# SCH_protopanda_v7.net
KiCad netlist of a schematic drawn in EasyEDA
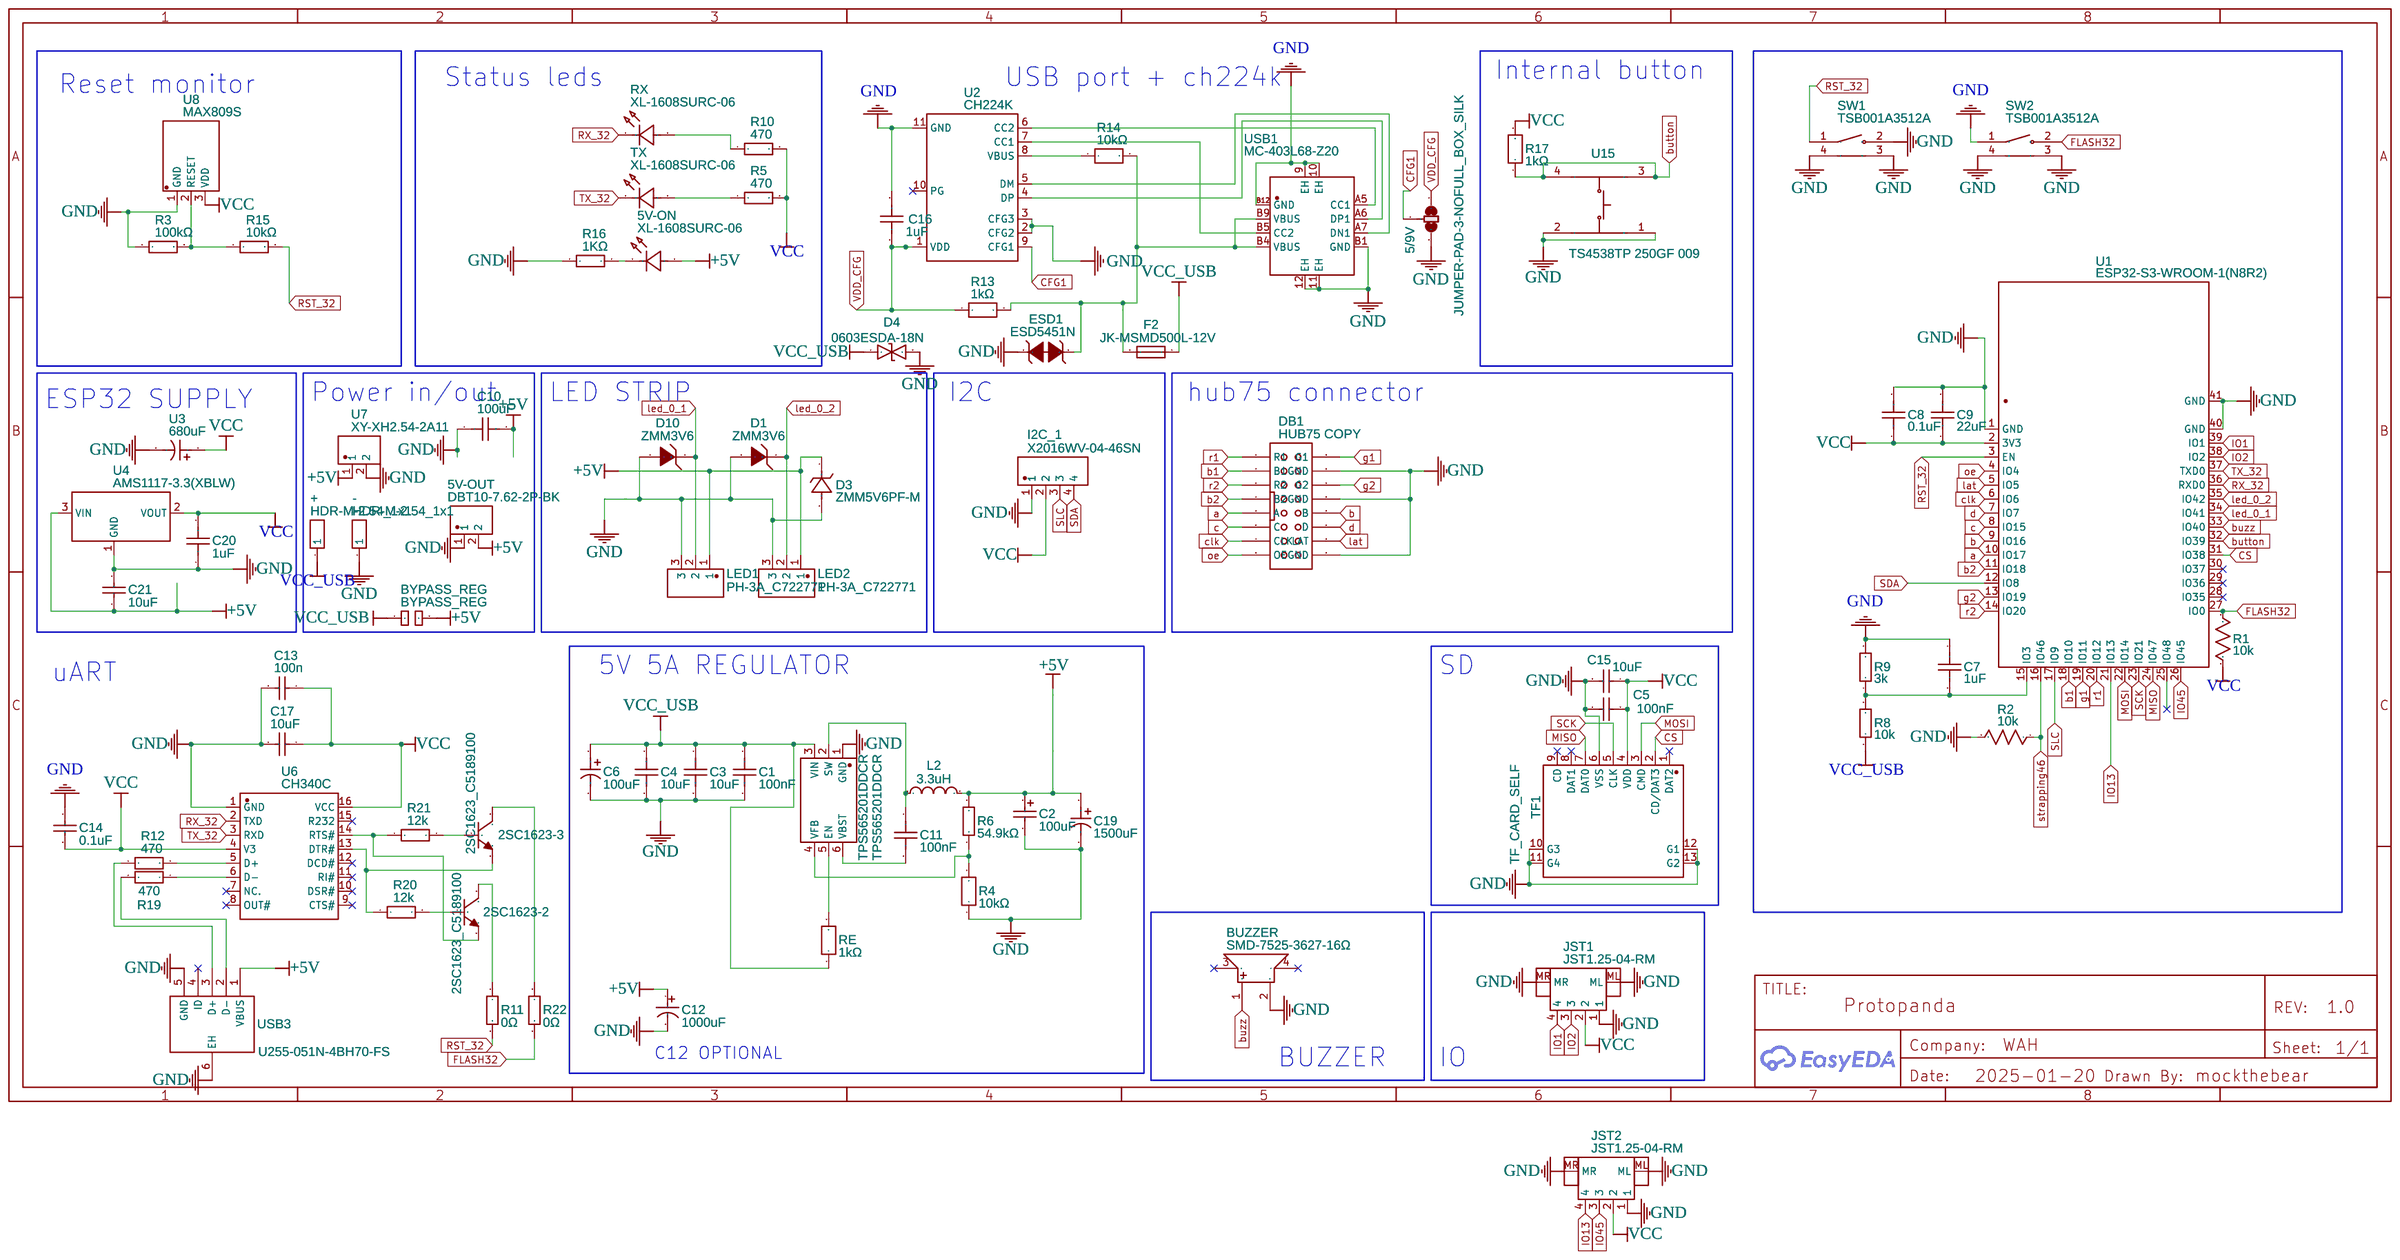
[diagram p0: schematic sheet]

(export (version "E")
  (design (tool "Eeschema 10.0.6"))
  (components
    (comp (ref "+") (value "HDR-M-2.54_1x1") (libsource (lib "") (part "HDR-M-2.54_1x1")))
    (comp (ref "-") (value "HDR-M-2.54_1x1") (libsource (lib "") (part "HDR-M-2.54_1x1_1")))
    (comp (ref "2SC1623-2")
      (value "2SC1623_C5189100")
      (fields (field (name "Manufacturer Part") "2SC1623") (field (name "Manufacturer") "HXY MOSFET(华轩阳电子)"))
      (libsource (lib "") (part "2SC1623_C5189100"))
    )
    (comp (ref "2SC1623-3")
      (value "2SC1623_C5189100")
      (fields (field (name "Manufacturer Part") "2SC1623") (field (name "Manufacturer") "HXY MOSFET(华轩阳电子)"))
      (libsource (lib "") (part "2SC1623_C5189100"))
    )
    (comp (ref "5/9V")
      (value "JUMPER-PAD-3-NOFULL_BOX_SILK")
      (libsource (lib "") (part "JUMPER-PAD-3-NOFULL_BOX_SILK"))
    )
    (comp (ref "5V-ON")
      (value "XL-1608SURC-06")
      (fields (field (name "Manufacturer") "XINGLIGHT(成兴光)"))
      (libsource (lib "") (part "XL-1608SURC-06_1"))
    )
    (comp (ref "5V-OUT")
      (value "DBT10-7.62-2P-BK")
      (fields
        (field (name "Manufacturer Part") "DBT10-7.62-2P-BK-P")
        (field (name "Manufacturer") "DIBO(地博电气)")
      )
      (libsource (lib "") (part "DBT10-7.62-2P-BK"))
    )
    (comp (ref "BUZZER")
      (value "SMD-7525-3627-16Ω")
      (fields (field (name "Manufacturer") "S&S(海旭)"))
      (libsource (lib "") (part "SMD-7525-3627-16Ω"))
    )
    (comp (ref "BYPASS_REG") (value "BYPASS_REG") (libsource (lib "") (part "Jumper_Pad_2")))
    (comp (ref "C1")
      (value "100nF")
      (fields (field (name "Manufacturer Part") "CC0603CRNPO9BN5R1") (field (name "Manufacturer") "YAGEO"))
      (libsource (lib "") (part "CC0603CRNPO9BN5R1"))
    )
    (comp (ref "C2")
      (value "100uF")
      (fields
        (field (name "Manufacturer Part") "T490A107M006ATE800")
        (field (name "Manufacturer") "KEMET(基美)")
      )
      (libsource (lib "") (part "T490A107M006ATE800"))
    )
    (comp (ref "C3")
      (value "10uF")
      (fields (field (name "Manufacturer Part") "CC0603CRNPO9BN5R1") (field (name "Manufacturer") "YAGEO"))
      (libsource (lib "") (part "CC0603CRNPO9BN5R1"))
    )
    (comp (ref "C4")
      (value "10uF")
      (fields (field (name "Manufacturer Part") "CC0603CRNPO9BN5R1") (field (name "Manufacturer") "YAGEO"))
      (libsource (lib "") (part "CC0603CRNPO9BN5R1"))
    )
    (comp (ref "C5")
      (value "100nF")
      (fields (field (name "Manufacturer Part") "C0603X104K101T") (field (name "Manufacturer") "HEC"))
      (libsource (lib "") (part "C0603X104K101T"))
    )
    (comp (ref "C6")
      (value "100uF")
      (fields
        (field (name "Manufacturer Part") "RVT100UF25V67RV0011")
        (field (name "Manufacturer") "KNSCHA(科尼盛)")
      )
      (libsource (lib "") (part "RVT100UF25V67RV0011"))
    )
    (comp (ref "C7")
      (value "1uF")
      (fields
        (field (name "Manufacturer Part") "CS1608X7R105K250NRB")
        (field (name "Manufacturer") "Samwha Capacitor")
      )
      (libsource (lib "") (part "CS1608X7R105K250NRB_1"))
    )
    (comp (ref "C8")
      (value "0.1uF")
      (fields
        (field (name "Manufacturer Part") "0603BB104K500NGT")
        (field (name "Manufacturer") "Knowles(楼氏)")
      )
      (libsource (lib "") (part "0603BB104K500NGT"))
    )
    (comp (ref "C9")
      (value "22uF")
      (fields
        (field (name "Manufacturer Part") "GRM188R61A226ME15D")
        (field (name "Manufacturer") "muRata(村田)")
      )
      (libsource (lib "") (part "GRM188R61A226ME15D"))
    )
    (comp (ref "C10")
      (value "100uF")
      (fields
        (field (name "Manufacturer Part") "TCC1206X5R107M6R3HT")
        (field (name "Manufacturer") "CCTC(三环)")
      )
      (libsource (lib "") (part "TCC1206X5R107M6R3HT"))
    )
    (comp (ref "C11")
      (value "100nF")
      (fields (field (name "Manufacturer Part") "CC0603CRNPO9BN5R1") (field (name "Manufacturer") "YAGEO"))
      (libsource (lib "") (part "CC0603CRNPO9BN5R1"))
    )
    (comp (ref "C12")
      (value "1000uF")
      (fields
        (field (name "Manufacturer Part") "EEU-FC2A101")
        (field (name "Manufacturer") "Panasonic Electronic Components")
      )
      (libsource (lib "") (part "electrolytic_capacitor10UF5V"))
    )
    (comp (ref "C13")
      (value "100n")
      (fields (field (name "Manufacturer Part") "CC0603KRX5R5BB106") (field (name "Manufacturer") "YAGEO"))
      (libsource (lib "") (part "CC0603KRX5R5BB106_1"))
    )
    (comp (ref "C14")
      (value "0.1uF")
      (fields (field (name "Manufacturer Part") "CC0603KRX5R5BB106") (field (name "Manufacturer") "YAGEO"))
      (libsource (lib "") (part "CC0603KRX5R5BB106"))
    )
    (comp (ref "C15")
      (value "10uF")
      (fields (field (name "Manufacturer Part") "CC0603MRX5R6BB106") (field (name "Manufacturer") "YAGEO"))
      (libsource (lib "") (part "CC0603MRX5R6BB106"))
    )
    (comp (ref "C16")
      (value "1uF")
      (fields (field (name "Manufacturer Part") "CC0603CRNPO9BN5R1") (field (name "Manufacturer") "YAGEO"))
      (libsource (lib "") (part "CC0603CRNPO9BN5R1_1"))
    )
    (comp (ref "C17")
      (value "10uF")
      (fields (field (name "Manufacturer Part") "CC0603KRX5R5BB106") (field (name "Manufacturer") "YAGEO"))
      (libsource (lib "") (part "CC0603KRX5R5BB106_1"))
    )
    (comp (ref "C19")
      (value "1500uF")
      (fields (field (name "Manufacturer Part") "189RV0022") (field (name "Manufacturer") "KNSCHA(科尼盛)"))
      (libsource (lib "") (part "189RV0022"))
    )
    (comp (ref "C20")
      (value "1uF")
      (fields
        (field (name "Manufacturer Part") "CS1608X7R105K250NRB")
        (field (name "Manufacturer") "Samwha Capacitor")
      )
      (libsource (lib "") (part "CS1608X7R105K250NRB"))
    )
    (comp (ref "C21")
      (value "10uF")
      (fields (field (name "Manufacturer Part") "CC0603MRX5R6BB106") (field (name "Manufacturer") "YAGEO"))
      (libsource (lib "") (part "CC0603MRX5R6BB106_1"))
    )
    (comp (ref "D1")
      (value "ZMM3V6")
      (fields (field (name "Manufacturer Part") "ZMM3V6-M") (field (name "Manufacturer") "ST(先科)"))
      (libsource (lib "") (part "ZMM3V6"))
    )
    (comp (ref "D3")
      (value "ZMM5V6PF-M")
      (fields (field (name "Manufacturer") "ST(先科)"))
      (libsource (lib "") (part "ZMM5V6PF-M"))
    )
    (comp (ref "D4")
      (value "0603ESDA-18N")
      (fields (field (name "Manufacturer") "BORN(伯恩半导体)"))
      (libsource (lib "") (part "0603ESDA-18N"))
    )
    (comp (ref "D10")
      (value "ZMM3V6")
      (fields (field (name "Manufacturer Part") "ZMM3V6-M") (field (name "Manufacturer") "ST(先科)"))
      (libsource (lib "") (part "ZMM3V6"))
    )
    (comp (ref "DB1") (value "HUB75 COPY") (libsource (lib "") (part "HUB75 COPY")))
    (comp (ref "ESD1")
      (value "ESD5451N")
      (fields (field (name "Manufacturer") "UMW(广东友台半导体)"))
      (libsource (lib "") (part "ESD5451N"))
    )
    (comp (ref "F2")
      (value "JK-MSMD500L-12V")
      (fields (field (name "Manufacturer") "JK(金科)"))
      (libsource (lib "") (part "JK-MSMD500L-12V"))
    )
    (comp (ref "I2C_1")
      (value "X2016WV-04-46SN")
      (fields (field (name "Manufacturer") "XKB Connectivity(中国星坤)"))
      (libsource (lib "") (part "X2016WV-04-46SN"))
    )
    (comp (ref "JST1") (value "JST1.25-04-RM") (libsource (lib "") (part "JST1.25-04-RM")))
    (comp (ref "JST2") (value "JST1.25-04-RM") (libsource (lib "") (part "JST1.25-04-RM")))
    (comp (ref "L2")
      (value "3.3uH")
      (fields
        (field (name "Manufacturer Part") "PSPMAA1040H-3R3M-ANP")
        (field (name "Manufacturer") "PROD(谱罗德)")
      )
      (libsource (lib "") (part "PSPMAA1040H-3R3M-ANP"))
    )
    (comp (ref "LED1")
      (value "PH-3A_C722771")
      (fields (field (name "Manufacturer Part") "PH-3A") (field (name "Manufacturer") "CAX(创都)"))
      (libsource (lib "") (part "PH-3A_C722771"))
    )
    (comp (ref "LED2")
      (value "PH-3A_C722771")
      (fields (field (name "Manufacturer Part") "PH-3A") (field (name "Manufacturer") "CAX(创都)"))
      (libsource (lib "") (part "PH-3A_C722771"))
    )
    (comp (ref "R1") (value "10k") (libsource (lib "") (part "R_0603_US_1")))
    (comp (ref "R2") (value "10k") (libsource (lib "") (part "R_0603_US")))
    (comp (ref "R3")
      (value "100kΩ")
      (fields
        (field (name "Manufacturer Part") "PTFR0603B10K0P9")
        (field (name "Manufacturer") "ResistorToday")
      )
      (libsource (lib "") (part "PTFR0603B10K0P9"))
    )
    (comp (ref "R4")
      (value "10kΩ")
      (fields (field (name "Manufacturer Part") "FRC0603F4992TS") (field (name "Manufacturer") "FOJAN(富捷)"))
      (libsource (lib "") (part "FRC0603F4992TS_2"))
    )
    (comp (ref "R5")
      (value "470")
      (fields (field (name "Manufacturer Part") "CR0603FA56R0G") (field (name "Manufacturer") "LIZ"))
      (libsource (lib "") (part "CR0603FA56R0G"))
    )
    (comp (ref "R6")
      (value "54.9kΩ")
      (fields
        (field (name "Manufacturer Part") "RCT03365KFLF")
        (field (name "Manufacturer") "Hong Kong Resistors")
      )
      (libsource (lib "") (part "RCT03365KFLF"))
    )
    (comp (ref "R8")
      (value "10k")
      (fields (field (name "Manufacturer Part") "CR0603FA56R0G") (field (name "Manufacturer") "LIZ"))
      (libsource (lib "") (part "CR0603FA56R0G_1"))
    )
    (comp (ref "R9")
      (value "3k")
      (fields (field (name "Manufacturer Part") "CR0603FA56R0G") (field (name "Manufacturer") "LIZ"))
      (libsource (lib "") (part "CR0603FA56R0G_1"))
    )
    (comp (ref "R10")
      (value "470")
      (fields (field (name "Manufacturer Part") "CR0603FA56R0G") (field (name "Manufacturer") "LIZ"))
      (libsource (lib "") (part "CR0603FA56R0G"))
    )
    (comp (ref "R11")
      (value "0Ω")
      (fields
        (field (name "Manufacturer Part") "AECR0603F100RK9")
        (field (name "Manufacturer") "ResistorToday")
      )
      (libsource (lib "") (part "AECR0603F100RK9"))
    )
    (comp (ref "R12")
      (value "470")
      (fields (field (name "Manufacturer Part") "CR0603FA56R0G") (field (name "Manufacturer") "LIZ"))
      (libsource (lib "") (part "CR0603FA56R0G"))
    )
    (comp (ref "R13")
      (value "1kΩ")
      (fields (field (name "Manufacturer Part") "FRC0603F4992TS") (field (name "Manufacturer") "FOJAN(富捷)"))
      (libsource (lib "") (part "FRC0603F4992TS_1"))
    )
    (comp (ref "R14")
      (value "10kΩ")
      (fields (field (name "Manufacturer Part") "FRC0603F4992TS") (field (name "Manufacturer") "FOJAN(富捷)"))
      (libsource (lib "") (part "FRC0603F4992TS_1"))
    )
    (comp (ref "R15")
      (value "10kΩ")
      (fields
        (field (name "Manufacturer Part") "PTFR0603B10K0P9")
        (field (name "Manufacturer") "ResistorToday")
      )
      (libsource (lib "") (part "PTFR0603B10K0P9"))
    )
    (comp (ref "R16")
      (value "1KΩ")
      (fields (field (name "Manufacturer Part") "CR0603FA56R0G") (field (name "Manufacturer") "LIZ"))
      (libsource (lib "") (part "CR0603FA56R0G"))
    )
    (comp (ref "R17")
      (value "1kΩ")
      (fields (field (name "Manufacturer Part") "FRC0603F4992TS") (field (name "Manufacturer") "FOJAN(富捷)"))
      (libsource (lib "") (part "FRC0603F4992TS_2"))
    )
    (comp (ref "R19")
      (value "470")
      (fields (field (name "Manufacturer Part") "CR0603FA56R0G") (field (name "Manufacturer") "LIZ"))
      (libsource (lib "") (part "CR0603FA56R0G_2"))
    )
    (comp (ref "R20")
      (value "12k")
      (fields (field (name "Manufacturer Part") "CR0603FA56R0G") (field (name "Manufacturer") "LIZ"))
      (libsource (lib "") (part "CR0603FA56R0G"))
    )
    (comp (ref "R21")
      (value "12k")
      (fields (field (name "Manufacturer Part") "CR0603FA56R0G") (field (name "Manufacturer") "LIZ"))
      (libsource (lib "") (part "CR0603FA56R0G"))
    )
    (comp (ref "R22")
      (value "0Ω")
      (fields
        (field (name "Manufacturer Part") "AECR0603F100RK9")
        (field (name "Manufacturer") "ResistorToday")
      )
      (libsource (lib "") (part "AECR0603F100RK9_1"))
    )
    (comp (ref "RE")
      (value "1kΩ")
      (fields (field (name "Manufacturer Part") "FRC0603F4992TS") (field (name "Manufacturer") "FOJAN(富捷)"))
      (libsource (lib "") (part "FRC0603F4992TS"))
    )
    (comp (ref "RX")
      (value "XL-1608SURC-06")
      (fields (field (name "Manufacturer") "XINGLIGHT(成兴光)"))
      (libsource (lib "") (part "XL-1608SURC-06"))
    )
    (comp (ref "SW1")
      (value "TSB001A3512A")
      (fields (field (name "Manufacturer") "BZCN(博众电气)"))
      (libsource (lib "") (part "TSB001A3512A"))
    )
    (comp (ref "SW2")
      (value "TSB001A3512A")
      (fields (field (name "Manufacturer") "BZCN(博众电气)"))
      (libsource (lib "") (part "TSB001A3512A"))
    )
    (comp (ref "TF1") (value "TF_CARD_SELF") (libsource (lib "") (part "TF_CARD_SELF")))
    (comp (ref "TPS565201DDCR")
      (value "TPS565201DDCR")
      (fields (field (name "Manufacturer") "TI(德州仪器)"))
      (libsource (lib "") (part "TPS565201DDCR"))
    )
    (comp (ref "TX")
      (value "XL-1608SURC-06")
      (fields (field (name "Manufacturer") "XINGLIGHT(成兴光)"))
      (libsource (lib "") (part "XL-1608SURC-06_2"))
    )
    (comp (ref "U1")
      (value "ESP32-S3-WROOM-1(N8R2)")
      (fields
        (field (name "Manufacturer Part") "ESP32-S3-WROOM-1-N8R2")
        (field (name "Manufacturer") "ESPRESSIF(乐鑫)")
      )
      (libsource (lib "") (part "ESP32-S3-WROOM-1(N8R2)"))
    )
    (comp (ref "U2")
      (value "CH224K")
      (fields (field (name "Manufacturer") "WCH(南京沁恒)"))
      (libsource (lib "") (part "CH224K"))
    )
    (comp (ref "U3")
      (value "680uF")
      (fields (field (name "Manufacturer Part") "189RV0015") (field (name "Manufacturer") "KNSCHA(科尼盛)"))
      (libsource (lib "") (part "189RV0015"))
    )
    (comp (ref "U4")
      (value "AMS1117-3.3(XBLW)")
      (fields (field (name "Manufacturer") "XBLW(芯伯乐)"))
      (libsource (lib "") (part "AMS1117-3.3(XBLW)"))
    )
    (comp (ref "U6")
      (value "CH340C")
      (fields (field (name "Manufacturer") "WCH(南京沁恒)"))
      (libsource (lib "") (part "CH340C"))
    )
    (comp (ref "U7")
      (value "XY-XH2.54-2A11")
      (fields (field (name "Manufacturer") "XYECONN(辛译)"))
      (libsource (lib "") (part "XY-XH2.54-2A11"))
    )
    (comp (ref "U8")
      (value "MAX809S")
      (fields (field (name "Manufacturer") "UMW(广东友台半导体)"))
      (libsource (lib "") (part "MAX809S"))
    )
    (comp (ref "U15")
      (value "TS4538TP 250GF 009")
      (fields
        (field (name "Manufacturer Part") "TS4538TP 250gf 009")
        (field (name "Manufacturer") "SHOU HAN(首韩)")
      )
      (libsource (lib "") (part "TS4538TP 250GF 009"))
    )
    (comp (ref "USB1")
      (value "MC-403L68-Z20")
      (fields (field (name "Manufacturer") "HANBO(汉博)"))
      (libsource (lib "") (part "MC-403L68-Z20"))
    )
    (comp (ref "USB3")
      (value "U255-051N-4BH70-FS")
      (fields (field (name "Manufacturer") "XKB Enterprise"))
      (libsource (lib "") (part "U255-051N-4BH70-FS"))
    )
  )
  (nets
    (net (code "1") (name "+5V") (class "Default")
      (node (ref "5V-ON") (pin "2") (pinfunction "A_2") (pintype "unspecified"))
      (node (ref "5V-OUT") (pin "2") (pinfunction "2_2") (pintype "unspecified"))
      (node (ref "BYPASS_REG") (pin "2") (pinfunction "2_2") (pintype "unspecified"))
      (node (ref "C10") (pin "2") (pinfunction "2_2") (pintype "unspecified"))
      (node (ref "C12") (pin "1") (pinfunction "1_1") (pintype "input"))
      (node (ref "C19") (pin "1") (pinfunction "1_1") (pintype "input"))
      (node (ref "C2") (pin "1") (pinfunction "1_1") (pintype "input"))
      (node (ref "C21") (pin "2") (pinfunction "2_2") (pintype "input"))
      (node (ref "D3") (pin "1") (pinfunction "C_1") (pintype "unspecified"))
      (node (ref "L2") (pin "2") (pinfunction "2_2") (pintype "unspecified"))
      (node (ref "LED1") (pin "1") (pinfunction "1_1") (pintype "unspecified"))
      (node (ref "LED2") (pin "1") (pinfunction "1_1") (pintype "unspecified"))
      (node (ref "R6") (pin "2") (pinfunction "2_2") (pintype "unspecified"))
      (node (ref "U4") (pin "3") (pinfunction "VIN_3") (pintype "unspecified"))
      (node (ref "U7") (pin "1") (pinfunction "1_1") (pintype "unspecified"))
      (node (ref "USB3") (pin "1") (pinfunction "VBUS_1") (pintype "unspecified"))
    )
    (net (code "2") (name "CFG1") (class "Default")
      (node (ref "5/9V") (pin "2") (pinfunction "2_2") (pintype "unspecified"))
      (node (ref "U2") (pin "9") (pinfunction "CFG1_9") (pintype "unspecified"))
    )
    (net (code "3") (name "CS") (class "Default")
      (node (ref "TF1") (pin "2") (pinfunction "CD/DAT3_2") (pintype "unspecified"))
      (node (ref "U1") (pin "31") (pinfunction "IO38_31") (pintype "unspecified"))
    )
    (net (code "4") (name "FLASH32") (class "Default")
      (node (ref "R1") (pin "2") (pinfunction "2_2") (pintype "unspecified"))
      (node (ref "R22") (pin "1") (pinfunction "1_1") (pintype "unspecified"))
      (node (ref "SW2") (pin "2") (pinfunction "2_2") (pintype "unspecified"))
      (node (ref "U1") (pin "27") (pinfunction "IO0_27") (pintype "unspecified"))
    )
    (net (code "5") (name "GND") (class "Default")
      (node (ref "-") (pin "1") (pinfunction "1_1") (pintype "input"))
      (node (ref "5/9V") (pin "3") (pinfunction "3_3") (pintype "unspecified"))
      (node (ref "5V-OUT") (pin "1") (pinfunction "1_1") (pintype "unspecified"))
      (node (ref "BUZZER") (pin "2") (pinfunction "2_2") (pintype "unspecified"))
      (node (ref "C1") (pin "2") (pinfunction "2_2") (pintype "unspecified"))
      (node (ref "C10") (pin "1") (pinfunction "1_1") (pintype "unspecified"))
      (node (ref "C12") (pin "2") (pinfunction "2_2") (pintype "input"))
      (node (ref "C13") (pin "2") (pinfunction "2_2") (pintype "input"))
      (node (ref "C14") (pin "1") (pinfunction "1_1") (pintype "input"))
      (node (ref "C15") (pin "2") (pinfunction "2_2") (pintype "input"))
      (node (ref "C16") (pin "2") (pinfunction "2_2") (pintype "unspecified"))
      (node (ref "C17") (pin "2") (pinfunction "2_2") (pintype "input"))
      (node (ref "C19") (pin "2") (pinfunction "2_2") (pintype "input"))
      (node (ref "C2") (pin "2") (pinfunction "2_2") (pintype "input"))
      (node (ref "C20") (pin "1") (pinfunction "1_1") (pintype "unspecified"))
      (node (ref "C21") (pin "1") (pinfunction "1_1") (pintype "input"))
      (node (ref "C3") (pin "2") (pinfunction "2_2") (pintype "unspecified"))
      (node (ref "C4") (pin "2") (pinfunction "2_2") (pintype "unspecified"))
      (node (ref "C5") (pin "1") (pinfunction "1_1") (pintype "input"))
      (node (ref "C6") (pin "2") (pinfunction "2_2") (pintype "input"))
      (node (ref "C7") (pin "1") (pinfunction "1_1") (pintype "unspecified"))
      (node (ref "C8") (pin "2") (pinfunction "2_2") (pintype "unspecified"))
      (node (ref "C9") (pin "1") (pinfunction "1_1") (pintype "unspecified"))
      (node (ref "D1") (pin "2") (pinfunction "A_2") (pintype "unspecified"))
      (node (ref "D10") (pin "2") (pinfunction "A_2") (pintype "unspecified"))
      (node (ref "D3") (pin "2") (pinfunction "A_2") (pintype "unspecified"))
      (node (ref "D4") (pin "2") (pinfunction "2_2") (pintype "unspecified"))
      (node (ref "DB1") (pin "13") (pinfunction "GND_13") (pintype "unspecified"))
      (node (ref "DB1") (pin "15") (pinfunction "GND_15") (pintype "unspecified"))
      (node (ref "DB1") (pin "9") (pinfunction "GND_9") (pintype "unspecified"))
      (node (ref "ESD1") (pin "1") (pinfunction "1_1") (pintype "unspecified"))
      (node (ref "I2C_1") (pin "1") (pinfunction "1_1") (pintype "unspecified"))
      (node (ref "JST1") (pin "1") (pinfunction "1_1") (pintype "unspecified"))
      (node (ref "JST1") (pin "ML") (pinfunction "ML_ML") (pintype "unspecified"))
      (node (ref "JST1") (pin "MR") (pinfunction "MR_MR") (pintype "unspecified"))
      (node (ref "JST2") (pin "1") (pinfunction "1_1") (pintype "unspecified"))
      (node (ref "JST2") (pin "ML") (pinfunction "ML_ML") (pintype "unspecified"))
      (node (ref "JST2") (pin "MR") (pinfunction "MR_MR") (pintype "unspecified"))
      (node (ref "LED1") (pin "3") (pinfunction "3_3") (pintype "unspecified"))
      (node (ref "LED2") (pin "3") (pinfunction "3_3") (pintype "unspecified"))
      (node (ref "R16") (pin "1") (pinfunction "1_1") (pintype "input"))
      (node (ref "R2") (pin "2") (pinfunction "2_2") (pintype "unspecified"))
      (node (ref "R3") (pin "1") (pinfunction "1_1") (pintype "unspecified"))
      (node (ref "R4") (pin "1") (pinfunction "1_1") (pintype "unspecified"))
      (node (ref "R9") (pin "2") (pinfunction "2_2") (pintype "input"))
      (node (ref "SW1") (pin "2") (pinfunction "2_2") (pintype "unspecified"))
      (node (ref "SW1") (pin "3") (pinfunction "3_3") (pintype "unspecified"))
      (node (ref "SW1") (pin "4") (pinfunction "4_4") (pintype "unspecified"))
      (node (ref "SW2") (pin "1") (pinfunction "1_1") (pintype "unspecified"))
      (node (ref "SW2") (pin "3") (pinfunction "3_3") (pintype "unspecified"))
      (node (ref "SW2") (pin "4") (pinfunction "4_4") (pintype "unspecified"))
      (node (ref "TF1") (pin "10") (pinfunction "G3_10") (pintype "unspecified"))
      (node (ref "TF1") (pin "11") (pinfunction "G4_11") (pintype "unspecified"))
      (node (ref "TF1") (pin "12") (pinfunction "G1_12") (pintype "unspecified"))
      (node (ref "TF1") (pin "13") (pinfunction "G2_13") (pintype "unspecified"))
      (node (ref "TF1") (pin "6") (pinfunction "VSS_6") (pintype "unspecified"))
      (node (ref "TPS565201DDCR") (pin "1") (pinfunction "GND_1") (pintype "unspecified"))
      (node (ref "U1") (pin "1") (pinfunction "GND_1") (pintype "unspecified"))
      (node (ref "U1") (pin "40") (pinfunction "GND_40") (pintype "unspecified"))
      (node (ref "U1") (pin "41") (pinfunction "GND_41") (pintype "unspecified"))
      (node (ref "U15") (pin "1") (pinfunction "1_1") (pintype "unspecified"))
      (node (ref "U15") (pin "2") (pinfunction "2_2") (pintype "unspecified"))
      (node (ref "U2") (pin "11") (pinfunction "GND_11") (pintype "unspecified"))
      (node (ref "U2") (pin "2") (pinfunction "CFG2_2") (pintype "unspecified"))
      (node (ref "U2") (pin "3") (pinfunction "CFG3_3") (pintype "unspecified"))
      (node (ref "U3") (pin "2") (pinfunction "2_2") (pintype "input"))
      (node (ref "U4") (pin "1") (pinfunction "GND_1") (pintype "unspecified"))
      (node (ref "U6") (pin "1") (pinfunction "GND_1") (pintype "unspecified"))
      (node (ref "U7") (pin "2") (pinfunction "2_2") (pintype "unspecified"))
      (node (ref "U8") (pin "1") (pinfunction "GND_1") (pintype "unspecified"))
      (node (ref "USB1") (pin "10") (pinfunction "EH_10") (pintype "unspecified"))
      (node (ref "USB1") (pin "11") (pinfunction "EH_11") (pintype "unspecified"))
      (node (ref "USB1") (pin "12") (pinfunction "EH_12") (pintype "unspecified"))
      (node (ref "USB1") (pin "9") (pinfunction "EH_9") (pintype "unspecified"))
      (node (ref "USB1") (pin "B1") (pinfunction "GND_B1") (pintype "unspecified"))
      (node (ref "USB1") (pin "B12") (pinfunction "GND_B12") (pintype "unspecified"))
      (node (ref "USB3") (pin "5") (pinfunction "GND_5") (pintype "unspecified"))
      (node (ref "USB3") (pin "6") (pinfunction "EH_6") (pintype "unspecified"))
    )
    (net (code "6") (name "IO1") (class "Default")
      (node (ref "JST1") (pin "4") (pinfunction "4_4") (pintype "unspecified"))
      (node (ref "U1") (pin "39") (pinfunction "IO1_39") (pintype "unspecified"))
    )
    (net (code "7") (name "IO2") (class "Default")
      (node (ref "JST1") (pin "3") (pinfunction "3_3") (pintype "unspecified"))
      (node (ref "U1") (pin "38") (pinfunction "IO2_38") (pintype "unspecified"))
    )
    (net (code "8") (name "IO13") (class "Default")
      (node (ref "JST2") (pin "4") (pinfunction "4_4") (pintype "unspecified"))
      (node (ref "U1") (pin "21") (pinfunction "IO13_21") (pintype "unspecified"))
    )
    (net (code "9") (name "IO45") (class "Default")
      (node (ref "JST2") (pin "3") (pinfunction "3_3") (pintype "unspecified"))
      (node (ref "U1") (pin "26") (pinfunction "IO45_26") (pintype "unspecified"))
    )
    (net (code "10") (name "MISO") (class "Default")
      (node (ref "TF1") (pin "7") (pinfunction "DAT0_7") (pintype "unspecified"))
      (node (ref "U1") (pin "24") (pinfunction "IO47_24") (pintype "unspecified"))
    )
    (net (code "11") (name "MOSI") (class "Default")
      (node (ref "TF1") (pin "3") (pinfunction "CMD_3") (pintype "unspecified"))
      (node (ref "U1") (pin "22") (pinfunction "IO14_22") (pintype "unspecified"))
    )
    (net (code "12") (name "Net-(2SC1623-2-B)") (class "Default")
      (node (ref "2SC1623-2") (pin "1") (pinfunction "B_1") (pintype "input"))
      (node (ref "R20") (pin "2") (pinfunction "2_2") (pintype "input"))
    )
    (net (code "13") (name "Net-(2SC1623-2-C)") (class "Default")
      (node (ref "2SC1623-2") (pin "3") (pinfunction "C_3") (pintype "input"))
      (node (ref "R11") (pin "1") (pinfunction "1_1") (pintype "unspecified"))
    )
    (net (code "14") (name "Net-(2SC1623-2-E)") (class "Default")
      (node (ref "2SC1623-2") (pin "2") (pinfunction "E_2") (pintype "input"))
      (node (ref "R21") (pin "1") (pinfunction "1_1") (pintype "input"))
      (node (ref "U6") (pin "14") (pinfunction "RTS#_14") (pintype "unspecified"))
    )
    (net (code "15") (name "Net-(2SC1623-3-B)") (class "Default")
      (node (ref "2SC1623-3") (pin "1") (pinfunction "B_1") (pintype "input"))
      (node (ref "R21") (pin "2") (pinfunction "2_2") (pintype "input"))
    )
    (net (code "16") (name "Net-(2SC1623-3-C)") (class "Default")
      (node (ref "2SC1623-3") (pin "3") (pinfunction "C_3") (pintype "input"))
      (node (ref "R22") (pin "2") (pinfunction "2_2") (pintype "unspecified"))
    )
    (net (code "17") (name "Net-(2SC1623-3-E)") (class "Default")
      (node (ref "2SC1623-3") (pin "2") (pinfunction "E_2") (pintype "input"))
      (node (ref "R20") (pin "1") (pinfunction "1_1") (pintype "input"))
      (node (ref "U6") (pin "13") (pinfunction "DTR#_13") (pintype "unspecified"))
    )
    (net (code "18") (name "Net-(5V-ON-K)") (class "Default")
      (node (ref "5V-ON") (pin "1") (pinfunction "K_1") (pintype "unspecified"))
      (node (ref "R16") (pin "2") (pinfunction "2_2") (pintype "input"))
    )
    (net (code "19") (name "Net-(ESD1-Pad2)") (class "Default")
      (node (ref "ESD1") (pin "2") (pinfunction "2_2") (pintype "unspecified"))
      (node (ref "F2") (pin "2") (pinfunction "2_2") (pintype "unspecified"))
      (node (ref "R13") (pin "2") (pinfunction "2_2") (pintype "unspecified"))
      (node (ref "R14") (pin "2") (pinfunction "2_2") (pintype "unspecified"))
      (node (ref "USB1") (pin "B4") (pinfunction "VBUS_B4") (pintype "unspecified"))
      (node (ref "USB1") (pin "B9") (pinfunction "VBUS_B9") (pintype "unspecified"))
    )
    (net (code "20") (name "Net-(RX-A)") (class "Default")
      (node (ref "R10") (pin "1") (pinfunction "1_1") (pintype "input"))
      (node (ref "RX") (pin "2") (pinfunction "A_2") (pintype "unspecified"))
    )
    (net (code "21") (name "Net-(TPS565201DDCR-EN)") (class "Default")
      (node (ref "RE") (pin "2") (pinfunction "2_2") (pintype "unspecified"))
      (node (ref "TPS565201DDCR") (pin "5") (pinfunction "EN_5") (pintype "unspecified"))
    )
    (net (code "22") (name "Net-(TPS565201DDCR-SW)") (class "Default")
      (node (ref "C11") (pin "1") (pinfunction "1_1") (pintype "unspecified"))
      (node (ref "L2") (pin "1") (pinfunction "1_1") (pintype "unspecified"))
      (node (ref "TPS565201DDCR") (pin "2") (pinfunction "SW_2") (pintype "unspecified"))
    )
    (net (code "23") (name "Net-(TPS565201DDCR-VBST)") (class "Default")
      (node (ref "C11") (pin "2") (pinfunction "2_2") (pintype "unspecified"))
      (node (ref "TPS565201DDCR") (pin "6") (pinfunction "VBST_6") (pintype "unspecified"))
    )
    (net (code "24") (name "Net-(TPS565201DDCR-VFB)") (class "Default")
      (node (ref "R4") (pin "2") (pinfunction "2_2") (pintype "unspecified"))
      (node (ref "R6") (pin "1") (pinfunction "1_1") (pintype "unspecified"))
      (node (ref "TPS565201DDCR") (pin "4") (pinfunction "VFB_4") (pintype "unspecified"))
    )
    (net (code "25") (name "Net-(TX-A)") (class "Default")
      (node (ref "R5") (pin "1") (pinfunction "1_1") (pintype "input"))
      (node (ref "TX") (pin "2") (pinfunction "A_2") (pintype "unspecified"))
    )
    (net (code "26") (name "Net-(U1-IO3)") (class "Default")
      (node (ref "C7") (pin "2") (pinfunction "2_2") (pintype "unspecified"))
      (node (ref "R8") (pin "2") (pinfunction "2_2") (pintype "input"))
      (node (ref "R9") (pin "1") (pinfunction "1_1") (pintype "input"))
      (node (ref "U1") (pin "15") (pinfunction "IO3_15") (pintype "unspecified"))
    )
    (net (code "27") (name "Net-(U2-CC1)") (class "Default")
      (node (ref "U2") (pin "7") (pinfunction "CC1_7") (pintype "unspecified"))
      (node (ref "USB1") (pin "B5") (pinfunction "CC2_B5") (pintype "unspecified"))
    )
    (net (code "28") (name "Net-(U2-CC2)") (class "Default")
      (node (ref "U2") (pin "6") (pinfunction "CC2_6") (pintype "unspecified"))
      (node (ref "USB1") (pin "A5") (pinfunction "CC1_A5") (pintype "unspecified"))
    )
    (net (code "29") (name "Net-(U2-DM)") (class "Default")
      (node (ref "U2") (pin "5") (pinfunction "DM_5") (pintype "unspecified"))
      (node (ref "USB1") (pin "A7") (pinfunction "DN1_A7") (pintype "unspecified"))
    )
    (net (code "30") (name "Net-(U2-DP)") (class "Default")
      (node (ref "U2") (pin "4") (pinfunction "DP_4") (pintype "unspecified"))
      (node (ref "USB1") (pin "A6") (pinfunction "DP1_A6") (pintype "unspecified"))
    )
    (net (code "31") (name "Net-(U2-VBUS)") (class "Default")
      (node (ref "R14") (pin "1") (pinfunction "1_1") (pintype "unspecified"))
      (node (ref "U2") (pin "8") (pinfunction "VBUS_8") (pintype "unspecified"))
    )
    (net (code "32") (name "Net-(U6-D+)") (class "Default")
      (node (ref "R12") (pin "2") (pinfunction "2_2") (pintype "input"))
      (node (ref "U6") (pin "5") (pinfunction "D+_5") (pintype "unspecified"))
    )
    (net (code "33") (name "Net-(U6-D-)") (class "Default")
      (node (ref "R19") (pin "1") (pinfunction "1_1") (pintype "input"))
      (node (ref "U6") (pin "6") (pinfunction "D-_6") (pintype "unspecified"))
    )
    (net (code "34") (name "Net-(U8-RESET)") (class "Default")
      (node (ref "R15") (pin "1") (pinfunction "1_1") (pintype "unspecified"))
      (node (ref "R3") (pin "2") (pinfunction "2_2") (pintype "unspecified"))
      (node (ref "U8") (pin "2") (pinfunction "RESET_2") (pintype "unspecified"))
    )
    (net (code "35") (name "Net-(USB3-D+)") (class "Default")
      (node (ref "R12") (pin "1") (pinfunction "1_1") (pintype "input"))
      (node (ref "USB3") (pin "3") (pinfunction "D+_3") (pintype "unspecified"))
    )
    (net (code "36") (name "Net-(USB3-D-)") (class "Default")
      (node (ref "R19") (pin "2") (pinfunction "2_2") (pintype "input"))
      (node (ref "USB3") (pin "2") (pinfunction "D-_2") (pintype "unspecified"))
    )
    (net (code "37") (name "RST_32") (class "Default")
      (node (ref "R11") (pin "2") (pinfunction "2_2") (pintype "unspecified"))
      (node (ref "R15") (pin "2") (pinfunction "2_2") (pintype "unspecified"))
      (node (ref "SW1") (pin "1") (pinfunction "1_1") (pintype "unspecified"))
      (node (ref "U1") (pin "3") (pinfunction "EN_3") (pintype "unspecified"))
    )
    (net (code "38") (name "RX_32") (class "Default")
      (node (ref "RX") (pin "1") (pinfunction "K_1") (pintype "unspecified"))
      (node (ref "U1") (pin "36") (pinfunction "RXD0_36") (pintype "unspecified"))
      (node (ref "U6") (pin "2") (pinfunction "TXD_2") (pintype "unspecified"))
    )
    (net (code "39") (name "SCK") (class "Default")
      (node (ref "TF1") (pin "5") (pinfunction "CLK_5") (pintype "unspecified"))
      (node (ref "U1") (pin "23") (pinfunction "IO21_23") (pintype "unspecified"))
    )
    (net (code "40") (name "SDA") (class "Default")
      (node (ref "I2C_1") (pin "4") (pinfunction "4_4") (pintype "unspecified"))
      (node (ref "U1") (pin "12") (pinfunction "IO8_12") (pintype "unspecified"))
    )
    (net (code "41") (name "SLC") (class "Default")
      (node (ref "I2C_1") (pin "3") (pinfunction "3_3") (pintype "unspecified"))
      (node (ref "U1") (pin "17") (pinfunction "IO9_17") (pintype "unspecified"))
    )
    (net (code "42") (name "TX_32") (class "Default")
      (node (ref "TX") (pin "1") (pinfunction "K_1") (pintype "unspecified"))
      (node (ref "U1") (pin "37") (pinfunction "TXD0_37") (pintype "unspecified"))
      (node (ref "U6") (pin "3") (pinfunction "RXD_3") (pintype "unspecified"))
    )
    (net (code "43") (name "VCC") (class "Default")
      (node (ref "C13") (pin "1") (pinfunction "1_1") (pintype "input"))
      (node (ref "C14") (pin "2") (pinfunction "2_2") (pintype "input"))
      (node (ref "C15") (pin "1") (pinfunction "1_1") (pintype "input"))
      (node (ref "C17") (pin "1") (pinfunction "1_1") (pintype "input"))
      (node (ref "C20") (pin "2") (pinfunction "2_2") (pintype "unspecified"))
      (node (ref "C5") (pin "2") (pinfunction "2_2") (pintype "input"))
      (node (ref "C8") (pin "1") (pinfunction "1_1") (pintype "unspecified"))
      (node (ref "C9") (pin "2") (pinfunction "2_2") (pintype "unspecified"))
      (node (ref "I2C_1") (pin "2") (pinfunction "2_2") (pintype "unspecified"))
      (node (ref "JST1") (pin "2") (pinfunction "2_2") (pintype "unspecified"))
      (node (ref "JST2") (pin "2") (pinfunction "2_2") (pintype "unspecified"))
      (node (ref "R1") (pin "1") (pinfunction "1_1") (pintype "unspecified"))
      (node (ref "R10") (pin "2") (pinfunction "2_2") (pintype "input"))
      (node (ref "R17") (pin "2") (pinfunction "2_2") (pintype "unspecified"))
      (node (ref "R5") (pin "2") (pinfunction "2_2") (pintype "input"))
      (node (ref "TF1") (pin "4") (pinfunction "VDD_4") (pintype "unspecified"))
      (node (ref "U1") (pin "2") (pinfunction "3V3_2") (pintype "unspecified"))
      (node (ref "U3") (pin "1") (pinfunction "1_1") (pintype "input"))
      (node (ref "U4") (pin "2") (pinfunction "VOUT_2") (pintype "unspecified"))
      (node (ref "U6") (pin "16") (pinfunction "VCC_16") (pintype "unspecified"))
      (node (ref "U6") (pin "4") (pinfunction "V3_4") (pintype "unspecified"))
      (node (ref "U8") (pin "3") (pinfunction "VDD_3") (pintype "unspecified"))
    )
    (net (code "44") (name "VCC_USB") (class "Default")
      (node (ref "+") (pin "1") (pinfunction "1_1") (pintype "input"))
      (node (ref "BYPASS_REG") (pin "1") (pinfunction "1_1") (pintype "unspecified"))
      (node (ref "C1") (pin "1") (pinfunction "1_1") (pintype "unspecified"))
      (node (ref "C3") (pin "1") (pinfunction "1_1") (pintype "unspecified"))
      (node (ref "C4") (pin "1") (pinfunction "1_1") (pintype "unspecified"))
      (node (ref "C6") (pin "1") (pinfunction "1_1") (pintype "input"))
      (node (ref "D4") (pin "1") (pinfunction "1_1") (pintype "unspecified"))
      (node (ref "F2") (pin "1") (pinfunction "1_1") (pintype "unspecified"))
      (node (ref "R8") (pin "1") (pinfunction "1_1") (pintype "input"))
      (node (ref "RE") (pin "1") (pinfunction "1_1") (pintype "unspecified"))
      (node (ref "TPS565201DDCR") (pin "3") (pinfunction "VIN_3") (pintype "unspecified"))
    )
    (net (code "45") (name "VDD_CFG") (class "Default")
      (node (ref "5/9V") (pin "1") (pinfunction "1_1") (pintype "unspecified"))
      (node (ref "C16") (pin "1") (pinfunction "1_1") (pintype "unspecified"))
      (node (ref "R13") (pin "1") (pinfunction "1_1") (pintype "unspecified"))
      (node (ref "U2") (pin "1") (pinfunction "VDD_1") (pintype "unspecified"))
    )
    (net (code "46") (name "a") (class "Default")
      (node (ref "DB1") (pin "5") (pinfunction "A_5") (pintype "unspecified"))
      (node (ref "U1") (pin "10") (pinfunction "IO17_10") (pintype "unspecified"))
    )
    (net (code "47") (name "b") (class "Default")
      (node (ref "DB1") (pin "12") (pinfunction "B_12") (pintype "unspecified"))
      (node (ref "U1") (pin "9") (pinfunction "IO16_9") (pintype "unspecified"))
    )
    (net (code "48") (name "b1") (class "Default")
      (node (ref "DB1") (pin "2") (pinfunction "B1_2") (pintype "unspecified"))
      (node (ref "U1") (pin "18") (pinfunction "IO10_18") (pintype "unspecified"))
    )
    (net (code "49") (name "b2") (class "Default")
      (node (ref "DB1") (pin "4") (pinfunction "B2_4") (pintype "unspecified"))
      (node (ref "U1") (pin "11") (pinfunction "IO18_11") (pintype "unspecified"))
    )
    (net (code "50") (name "button") (class "Default")
      (node (ref "R17") (pin "1") (pinfunction "1_1") (pintype "unspecified"))
      (node (ref "U1") (pin "32") (pinfunction "IO39_32") (pintype "unspecified"))
      (node (ref "U15") (pin "3") (pinfunction "3_3") (pintype "unspecified"))
      (node (ref "U15") (pin "4") (pinfunction "4_4") (pintype "unspecified"))
    )
    (net (code "51") (name "buzz") (class "Default")
      (node (ref "BUZZER") (pin "1") (pinfunction "1_1") (pintype "unspecified"))
      (node (ref "U1") (pin "33") (pinfunction "IO40_33") (pintype "unspecified"))
    )
    (net (code "52") (name "c") (class "Default")
      (node (ref "DB1") (pin "6") (pinfunction "C_6") (pintype "unspecified"))
      (node (ref "U1") (pin "8") (pinfunction "IO15_8") (pintype "unspecified"))
    )
    (net (code "53") (name "clk") (class "Default")
      (node (ref "DB1") (pin "7") (pinfunction "CLK_7") (pintype "unspecified"))
      (node (ref "U1") (pin "6") (pinfunction "IO6_6") (pintype "unspecified"))
    )
    (net (code "54") (name "d") (class "Default")
      (node (ref "DB1") (pin "11") (pinfunction "D_11") (pintype "unspecified"))
      (node (ref "U1") (pin "7") (pinfunction "IO7_7") (pintype "unspecified"))
    )
    (net (code "55") (name "g1") (class "Default")
      (node (ref "DB1") (pin "16") (pinfunction "G1_16") (pintype "unspecified"))
      (node (ref "U1") (pin "19") (pinfunction "IO11_19") (pintype "unspecified"))
    )
    (net (code "56") (name "g2") (class "Default")
      (node (ref "DB1") (pin "14") (pinfunction "G2_14") (pintype "unspecified"))
      (node (ref "U1") (pin "13") (pinfunction "IO19_13") (pintype "unspecified"))
    )
    (net (code "57") (name "lat") (class "Default")
      (node (ref "DB1") (pin "10") (pinfunction "LAT_10") (pintype "unspecified"))
      (node (ref "U1") (pin "5") (pinfunction "IO5_5") (pintype "unspecified"))
    )
    (net (code "58") (name "led_0_1") (class "Default")
      (node (ref "D10") (pin "1") (pinfunction "C_1") (pintype "unspecified"))
      (node (ref "LED1") (pin "2") (pinfunction "2_2") (pintype "unspecified"))
      (node (ref "U1") (pin "34") (pinfunction "IO41_34") (pintype "unspecified"))
    )
    (net (code "59") (name "led_0_2") (class "Default")
      (node (ref "D1") (pin "1") (pinfunction "C_1") (pintype "unspecified"))
      (node (ref "LED2") (pin "2") (pinfunction "2_2") (pintype "unspecified"))
      (node (ref "U1") (pin "35") (pinfunction "IO42_35") (pintype "unspecified"))
    )
    (net (code "60") (name "oe") (class "Default")
      (node (ref "DB1") (pin "8") (pinfunction "OE_8") (pintype "unspecified"))
      (node (ref "U1") (pin "4") (pinfunction "IO4_4") (pintype "unspecified"))
    )
    (net (code "61") (name "r1") (class "Default")
      (node (ref "DB1") (pin "1") (pinfunction "R1_1") (pintype "unspecified"))
      (node (ref "U1") (pin "20") (pinfunction "IO12_20") (pintype "unspecified"))
    )
    (net (code "62") (name "r2") (class "Default")
      (node (ref "DB1") (pin "3") (pinfunction "R2_3") (pintype "unspecified"))
      (node (ref "U1") (pin "14") (pinfunction "IO20_14") (pintype "unspecified"))
    )
    (net (code "63") (name "strapping46") (class "Default")
      (node (ref "R2") (pin "1") (pinfunction "1_1") (pintype "unspecified"))
      (node (ref "U1") (pin "16") (pinfunction "IO46_16") (pintype "unspecified"))
    )
    (net (code "64") (name "unconnected-(BUZZER-Pad3)") (class "Default")
      (node (ref "BUZZER") (pin "3") (pinfunction "3_3") (pintype "unspecified+no_connect"))
    )
    (net (code "65") (name "unconnected-(BUZZER-Pad4)") (class "Default")
      (node (ref "BUZZER") (pin "4") (pinfunction "4_4") (pintype "unspecified+no_connect"))
    )
    (net (code "66") (name "unconnected-(TF1-CD-Pad9)") (class "Default")
      (node (ref "TF1") (pin "9") (pinfunction "CD_9") (pintype "unspecified+no_connect"))
    )
    (net (code "67") (name "unconnected-(TF1-DAT1-Pad8)") (class "Default")
      (node (ref "TF1") (pin "8") (pinfunction "DAT1_8") (pintype "unspecified+no_connect"))
    )
    (net (code "68") (name "unconnected-(TF1-DAT2-Pad1)") (class "Default")
      (node (ref "TF1") (pin "1") (pinfunction "DAT2_1") (pintype "unspecified+no_connect"))
    )
    (net (code "69") (name "unconnected-(U1-IO35-Pad28)") (class "Default")
      (node (ref "U1") (pin "28") (pinfunction "IO35_28") (pintype "unspecified+no_connect"))
    )
    (net (code "70") (name "unconnected-(U1-IO36-Pad29)") (class "Default")
      (node (ref "U1") (pin "29") (pinfunction "IO36_29") (pintype "unspecified+no_connect"))
    )
    (net (code "71") (name "unconnected-(U1-IO37-Pad30)") (class "Default")
      (node (ref "U1") (pin "30") (pinfunction "IO37_30") (pintype "unspecified+no_connect"))
    )
    (net (code "72") (name "unconnected-(U1-IO48-Pad25)") (class "Default")
      (node (ref "U1") (pin "25") (pinfunction "IO48_25") (pintype "unspecified+no_connect"))
    )
    (net (code "73") (name "unconnected-(U2-PG-Pad10)") (class "Default")
      (node (ref "U2") (pin "10") (pinfunction "PG_10") (pintype "unspecified+no_connect"))
    )
    (net (code "74") (name "unconnected-(U6-CTS#-Pad9)") (class "Default")
      (node (ref "U6") (pin "9") (pinfunction "CTS#_9") (pintype "unspecified+no_connect"))
    )
    (net (code "75") (name "unconnected-(U6-DCD#-Pad12)") (class "Default")
      (node (ref "U6") (pin "12") (pinfunction "DCD#_12") (pintype "unspecified+no_connect"))
    )
    (net (code "76") (name "unconnected-(U6-DSR#-Pad10)") (class "Default")
      (node (ref "U6") (pin "10") (pinfunction "DSR#_10") (pintype "unspecified+no_connect"))
    )
    (net (code "77") (name "unconnected-(U6-NC.-Pad7)") (class "Default")
      (node (ref "U6") (pin "7") (pinfunction "NC._7") (pintype "unspecified+no_connect"))
    )
    (net (code "78") (name "unconnected-(U6-OUT#-Pad8)") (class "Default")
      (node (ref "U6") (pin "8") (pinfunction "OUT#_8") (pintype "unspecified+no_connect"))
    )
    (net (code "79") (name "unconnected-(U6-R232-Pad15)") (class "Default")
      (node (ref "U6") (pin "15") (pinfunction "R232_15") (pintype "unspecified+no_connect"))
    )
    (net (code "80") (name "unconnected-(U6-RI#-Pad11)") (class "Default")
      (node (ref "U6") (pin "11") (pinfunction "RI#_11") (pintype "unspecified+no_connect"))
    )
    (net (code "81") (name "unconnected-(USB3-ID-Pad4)") (class "Default")
      (node (ref "USB3") (pin "4") (pinfunction "ID_4") (pintype "unspecified+no_connect"))
    )
  )
)
